# am-crystal-rx.net
KiCad netlist of a schematic drawn in EAGLE
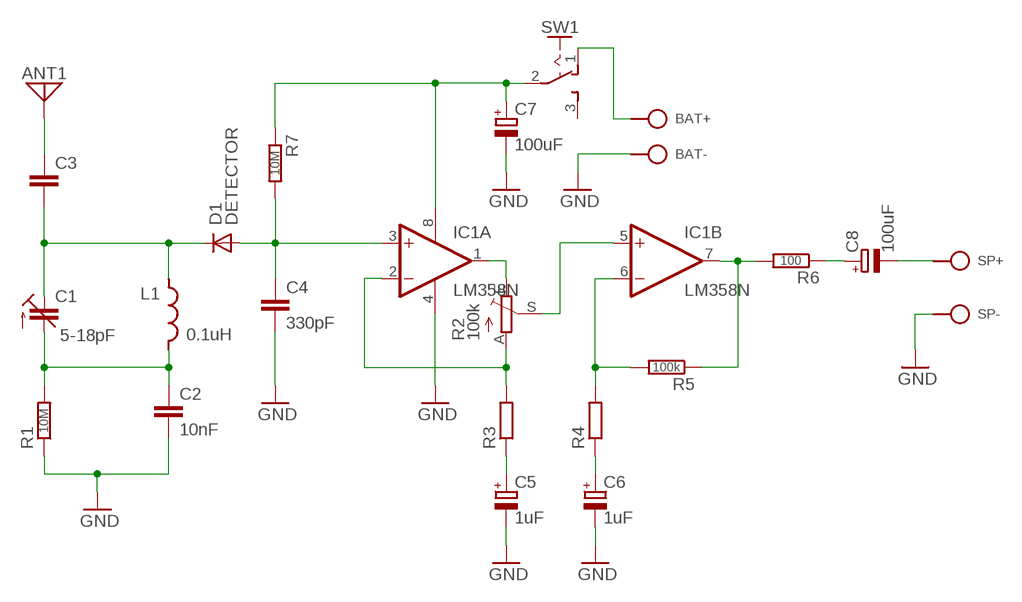
[diagram p0: schematic, sheet 1]

(export (version "E")
  (design (tool "Eeschema 10.0.6"))
  (components
    (comp (ref "ANT1")
      (value "ANT")
      (footprint "eagle-import:SPAD")
      (libsource (lib "eagle-import") (part "ANT"))
    )
    (comp (ref "BAT+")
      (value "BAT+")
      (footprint "eagle-import:SPAD")
      (libsource (lib "eagle-import") (part "SPAD"))
    )
    (comp (ref "BAT-")
      (value "BAT-")
      (footprint "eagle-import:SPAD")
      (libsource (lib "eagle-import") (part "SPAD"))
    )
    (comp (ref "C1")
      (value "5-18pF")
      (footprint "eagle-import:TRIM-2222-808")
      (libsource (lib "eagle-import") (part "C-TR-PH201272222-808-2PIN"))
    )
    (comp (ref "C2")
      (value "10nF")
      (footprint "eagle-import:C050-025X075")
      (libsource (lib "eagle-import") (part "C050-025X075"))
    )
    (comp (ref "C3")
      (value "C025-015X024")
      (footprint "eagle-import:C025-015X024")
      (libsource (lib "eagle-import") (part "C025-015X024"))
    )
    (comp (ref "C4")
      (value "330pF")
      (footprint "eagle-import:C050-024X044")
      (libsource (lib "eagle-import") (part "C050-024X044"))
    )
    (comp (ref "C5")
      (value "1uF")
      (footprint "eagle-import:E2,5-3")
      (libsource (lib "eagle-import") (part "CPOLE2,5-3"))
    )
    (comp (ref "C6")
      (value "1uF")
      (footprint "eagle-import:E2,5-3")
      (libsource (lib "eagle-import") (part "CPOLE2,5-3"))
    )
    (comp (ref "C7")
      (value "100uF")
      (footprint "eagle-import:E2,5-5")
      (libsource (lib "eagle-import") (part "CPOLE2.5-5"))
    )
    (comp (ref "C8")
      (value "100uF")
      (footprint "eagle-import:E2,5-5")
      (libsource (lib "eagle-import") (part "CPOLE2.5-5"))
    )
    (comp (ref "D1")
      (value "DETECTOR")
      (footprint "eagle-import:DO34-10")
      (libsource (lib "eagle-import") (part "1N414834-10"))
    )
    (comp (ref "IC1")
      (value "LM358N")
      (footprint "eagle-import:DIL08")
      (libsource (lib "eagle-import") (part "LM358N"))
    )
    (comp (ref "L1")
      (value "0.1uH")
      (footprint "eagle-import:L-04_10")
      (libsource (lib "eagle-import") (part "L-SHORT04/10"))
    )
    (comp (ref "R1")
      (value "10M")
      (footprint "eagle-import:0202_7-V")
      (libsource (lib "eagle-import") (part "R0202/7-V"))
    )
    (comp (ref "R2")
      (value "100k")
      (footprint "eagle-import:B64Y")
      (libsource (lib "eagle-import") (part "TRIM_EU-B64Y"))
    )
    (comp (ref "R3")
      (value "R0202/7")
      (footprint "eagle-import:0202_7")
      (libsource (lib "eagle-import") (part "R0202/7"))
    )
    (comp (ref "R4")
      (value "R0202/7")
      (footprint "eagle-import:0202_7")
      (libsource (lib "eagle-import") (part "R0202/7"))
    )
    (comp (ref "R5")
      (value "100k")
      (footprint "eagle-import:0202_7")
      (libsource (lib "eagle-import") (part "R0202/7"))
    )
    (comp (ref "R6")
      (value "100")
      (footprint "eagle-import:0202_7")
      (libsource (lib "eagle-import") (part "R0202/7"))
    )
    (comp (ref "R7")
      (value "10M")
      (footprint "eagle-import:0202_7")
      (libsource (lib "eagle-import") (part "R0202/7"))
    )
    (comp (ref "SP+")
      (value "SPKR+")
      (footprint "eagle-import:SPAD")
      (libsource (lib "eagle-import") (part "SPAD"))
    )
    (comp (ref "SP-")
      (value "SPKR-")
      (footprint "eagle-import:SPAD")
      (libsource (lib "eagle-import") (part "SPAD"))
    )
    (comp (ref "SW1")
      (value "SL-SW-1P-2T-H")
      (footprint "eagle-import:SLSW-1P2T-H")
      (libsource (lib "eagle-import") (part "SL-SW-1P-2T-H"))
    )
  )
  (nets
    (net (code "1") (name "GND") (class "Default")
      (node (ref "BAT-") (pin "1") (pinfunction "P$1_1") (pintype "bidirectional"))
      (node (ref "C2") (pin "2") (pinfunction "2_2") (pintype "passive"))
      (node (ref "C4") (pin "2") (pinfunction "2_2") (pintype "passive"))
      (node (ref "C5") (pin "-") (pinfunction "-_-") (pintype "passive"))
      (node (ref "C6") (pin "-") (pinfunction "-_-") (pintype "passive"))
      (node (ref "C7") (pin "-") (pinfunction "-_-") (pintype "passive"))
      (node (ref "IC1") (pin "4") (pinfunction "V-_4") (pintype "power_in"))
      (node (ref "R1") (pin "1") (pinfunction "1_1") (pintype "passive"))
      (node (ref "SP-") (pin "1") (pinfunction "P$1_1") (pintype "bidirectional"))
    )
    (net (code "2") (name "Net-(ANT1-Pad1)") (class "Default")
      (node (ref "ANT1") (pin "1") (pinfunction "1_1") (pintype "output"))
      (node (ref "C3") (pin "1") (pinfunction "1_1") (pintype "passive"))
    )
    (net (code "3") (name "Net-(BAT+-P$1)") (class "Default")
      (node (ref "BAT+") (pin "1") (pinfunction "P$1_1") (pintype "bidirectional"))
      (node (ref "SW1") (pin "1") (pinfunction "O_1") (pintype "passive"))
    )
    (net (code "4") (name "Net-(C1-A)") (class "Default")
      (node (ref "C1") (pin "1") (pinfunction "A_1") (pintype "passive"))
      (node (ref "C3") (pin "2") (pinfunction "2_2") (pintype "passive"))
      (node (ref "D1") (pin "C") (pinfunction "C_C") (pintype "passive"))
      (node (ref "L1") (pin "1") (pinfunction "1_1") (pintype "passive"))
    )
    (net (code "5") (name "Net-(C1-E)") (class "Default")
      (node (ref "C1") (pin "2") (pinfunction "E_2") (pintype "passive"))
      (node (ref "C2") (pin "1") (pinfunction "1_1") (pintype "passive"))
      (node (ref "L1") (pin "2") (pinfunction "2_2") (pintype "passive"))
      (node (ref "R1") (pin "2") (pinfunction "2_2") (pintype "passive"))
    )
    (net (code "6") (name "Net-(C5-Pad+)") (class "Default")
      (node (ref "C5") (pin "+") (pinfunction "+_+") (pintype "passive"))
      (node (ref "R3") (pin "1") (pinfunction "1_1") (pintype "passive"))
    )
    (net (code "7") (name "Net-(C6-Pad+)") (class "Default")
      (node (ref "C6") (pin "+") (pinfunction "+_+") (pintype "passive"))
      (node (ref "R4") (pin "1") (pinfunction "1_1") (pintype "passive"))
    )
    (net (code "8") (name "Net-(C8-Pad+)") (class "Default")
      (node (ref "C8") (pin "+") (pinfunction "+_+") (pintype "passive"))
      (node (ref "R6") (pin "1") (pinfunction "1_1") (pintype "passive"))
    )
    (net (code "9") (name "Net-(IC1A-+IN)") (class "Default")
      (node (ref "C4") (pin "1") (pinfunction "1_1") (pintype "passive"))
      (node (ref "D1") (pin "A") (pinfunction "A_A") (pintype "passive"))
      (node (ref "IC1") (pin "3") (pinfunction "+IN_3") (pintype "input"))
      (node (ref "R7") (pin "2") (pinfunction "2_2") (pintype "passive"))
    )
    (net (code "10") (name "Net-(IC1A--IN)") (class "Default")
      (node (ref "IC1") (pin "2") (pinfunction "-IN_2") (pintype "input"))
      (node (ref "R2") (pin "A") (pinfunction "A_A") (pintype "passive"))
      (node (ref "R3") (pin "2") (pinfunction "2_2") (pintype "passive"))
    )
    (net (code "11") (name "Net-(IC1A-OUT)") (class "Default")
      (node (ref "IC1") (pin "1") (pinfunction "OUT_1") (pintype "output"))
      (node (ref "R2") (pin "E") (pinfunction "E_E") (pintype "passive"))
    )
    (net (code "12") (name "Net-(IC1B-+IN)") (class "Default")
      (node (ref "IC1") (pin "5") (pinfunction "+IN_5") (pintype "input"))
      (node (ref "R2") (pin "S") (pinfunction "S_S") (pintype "passive"))
    )
    (net (code "13") (name "Net-(IC1B--IN)") (class "Default")
      (node (ref "IC1") (pin "6") (pinfunction "-IN_6") (pintype "input"))
      (node (ref "R4") (pin "2") (pinfunction "2_2") (pintype "passive"))
      (node (ref "R5") (pin "2") (pinfunction "2_2") (pintype "passive"))
    )
    (net (code "14") (name "Net-(IC1B-OUT)") (class "Default")
      (node (ref "IC1") (pin "7") (pinfunction "OUT_7") (pintype "output"))
      (node (ref "R5") (pin "1") (pinfunction "1_1") (pintype "passive"))
      (node (ref "R6") (pin "2") (pinfunction "2_2") (pintype "passive"))
    )
    (net (code "15") (name "Net-(IC1C-V+)") (class "Default")
      (node (ref "C7") (pin "+") (pinfunction "+_+") (pintype "passive"))
      (node (ref "IC1") (pin "8") (pinfunction "V+_8") (pintype "power_in"))
      (node (ref "R7") (pin "1") (pinfunction "1_1") (pintype "passive"))
      (node (ref "SW1") (pin "2") (pinfunction "P_2") (pintype "passive"))
    )
    (net (code "16") (name "Net-(SP+-P$1)") (class "Default")
      (node (ref "C8") (pin "-") (pinfunction "-_-") (pintype "passive"))
      (node (ref "SP+") (pin "1") (pinfunction "P$1_1") (pintype "bidirectional"))
    )
    (net (code "17") (name "unconnected-(SW1-S-Pad3)") (class "Default")
      (node (ref "SW1") (pin "3") (pinfunction "S_3") (pintype "passive"))
    )
  )
)
